# Jumper_Matrix.net
KiCad netlist of a schematic drawn in Altium Designer
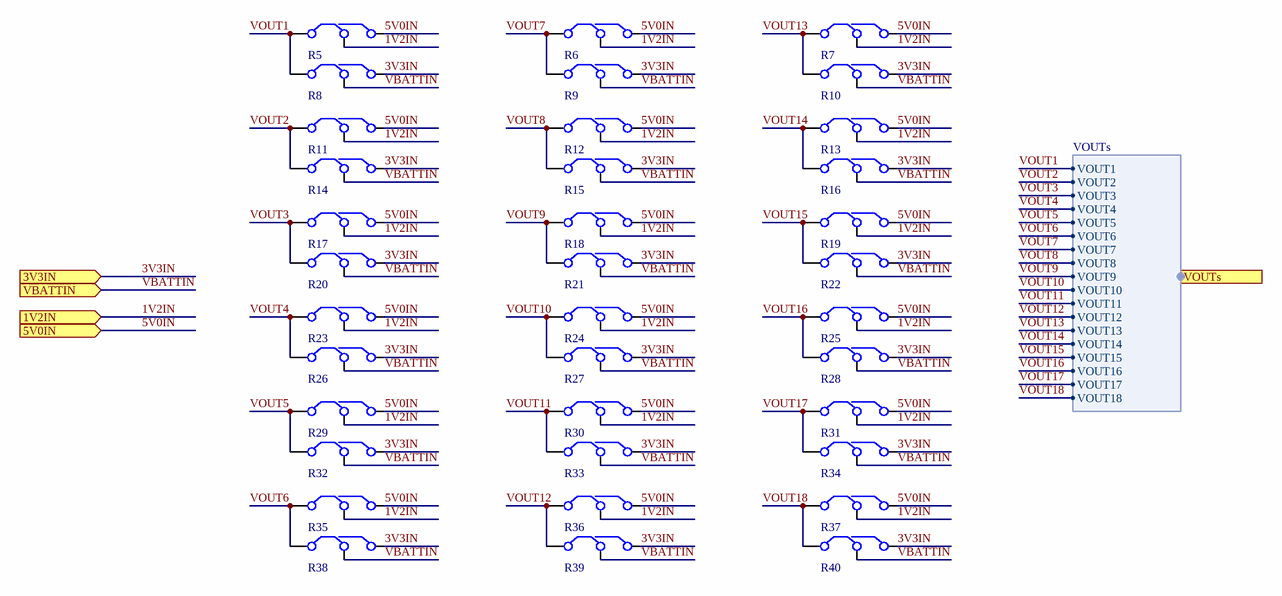
[diagram p0: Jumper Matrix.SchDoc]

(export (version "E")
  (design (tool "Eeschema 10.0.6"))
  (components
    (comp (ref "R5")
      (value "Jumper")
      (footprint "SKP-RMCF1210orRMCF2010")
      (libsource (lib "EPS") (part "PowerRailSelector"))
    )
    (comp (ref "R6")
      (value "Jumper")
      (footprint "SKP-RMCF1210orRMCF2010")
      (libsource (lib "EPS") (part "PowerRailSelector"))
    )
    (comp (ref "R7")
      (value "Jumper")
      (footprint "SKP-RMCF1210orRMCF2010")
      (libsource (lib "EPS") (part "PowerRailSelector"))
    )
    (comp (ref "R8")
      (value "Jumper")
      (footprint "SKP-RMCF1210orRMCF2010")
      (libsource (lib "EPS") (part "PowerRailSelector"))
    )
    (comp (ref "R9")
      (value "Jumper")
      (footprint "SKP-RMCF1210orRMCF2010")
      (libsource (lib "EPS") (part "PowerRailSelector"))
    )
    (comp (ref "R10")
      (value "Jumper")
      (footprint "SKP-RMCF1210orRMCF2010")
      (libsource (lib "EPS") (part "PowerRailSelector"))
    )
    (comp (ref "R11")
      (value "Jumper")
      (footprint "SKP-RMCF1210orRMCF2010")
      (libsource (lib "EPS") (part "PowerRailSelector"))
    )
    (comp (ref "R12")
      (value "Jumper")
      (footprint "SKP-RMCF1210orRMCF2010")
      (libsource (lib "EPS") (part "PowerRailSelector"))
    )
    (comp (ref "R13")
      (value "Jumper")
      (footprint "SKP-RMCF1210orRMCF2010")
      (libsource (lib "EPS") (part "PowerRailSelector"))
    )
    (comp (ref "R14")
      (value "Jumper")
      (footprint "SKP-RMCF1210orRMCF2010")
      (libsource (lib "EPS") (part "PowerRailSelector"))
    )
    (comp (ref "R15")
      (value "Jumper")
      (footprint "SKP-RMCF1210orRMCF2010")
      (libsource (lib "EPS") (part "PowerRailSelector"))
    )
    (comp (ref "R16")
      (value "Jumper")
      (footprint "SKP-RMCF1210orRMCF2010")
      (libsource (lib "EPS") (part "PowerRailSelector"))
    )
    (comp (ref "R17")
      (value "Jumper")
      (footprint "SKP-RMCF1210orRMCF2010")
      (libsource (lib "EPS") (part "PowerRailSelector"))
    )
    (comp (ref "R18")
      (value "Jumper")
      (footprint "SKP-RMCF1210orRMCF2010")
      (libsource (lib "EPS") (part "PowerRailSelector"))
    )
    (comp (ref "R19")
      (value "Jumper")
      (footprint "SKP-RMCF1210orRMCF2010")
      (libsource (lib "EPS") (part "PowerRailSelector"))
    )
    (comp (ref "R20")
      (value "Jumper")
      (footprint "SKP-RMCF1210orRMCF2010")
      (libsource (lib "EPS") (part "PowerRailSelector"))
    )
    (comp (ref "R21")
      (value "Jumper")
      (footprint "SKP-RMCF1210orRMCF2010")
      (libsource (lib "EPS") (part "PowerRailSelector"))
    )
    (comp (ref "R22")
      (value "Jumper")
      (footprint "SKP-RMCF1210orRMCF2010")
      (libsource (lib "EPS") (part "PowerRailSelector"))
    )
    (comp (ref "R23")
      (value "Jumper")
      (footprint "SKP-RMCF1210orRMCF2010")
      (libsource (lib "EPS") (part "PowerRailSelector"))
    )
    (comp (ref "R24")
      (value "Jumper")
      (footprint "SKP-RMCF1210orRMCF2010")
      (libsource (lib "EPS") (part "PowerRailSelector"))
    )
    (comp (ref "R25")
      (value "Jumper")
      (footprint "SKP-RMCF1210orRMCF2010")
      (libsource (lib "EPS") (part "PowerRailSelector"))
    )
    (comp (ref "R26")
      (value "Jumper")
      (footprint "SKP-RMCF1210orRMCF2010")
      (libsource (lib "EPS") (part "PowerRailSelector"))
    )
    (comp (ref "R27")
      (value "Jumper")
      (footprint "SKP-RMCF1210orRMCF2010")
      (libsource (lib "EPS") (part "PowerRailSelector"))
    )
    (comp (ref "R28")
      (value "Jumper")
      (footprint "SKP-RMCF1210orRMCF2010")
      (libsource (lib "EPS") (part "PowerRailSelector"))
    )
    (comp (ref "R29")
      (value "Jumper")
      (footprint "SKP-RMCF1210orRMCF2010")
      (libsource (lib "EPS") (part "PowerRailSelector"))
    )
    (comp (ref "R30")
      (value "Jumper")
      (footprint "SKP-RMCF1210orRMCF2010")
      (libsource (lib "EPS") (part "PowerRailSelector"))
    )
    (comp (ref "R31")
      (value "Jumper")
      (footprint "SKP-RMCF1210orRMCF2010")
      (libsource (lib "EPS") (part "PowerRailSelector"))
    )
    (comp (ref "R32")
      (value "Jumper")
      (footprint "SKP-RMCF1210orRMCF2010")
      (libsource (lib "EPS") (part "PowerRailSelector"))
    )
    (comp (ref "R33")
      (value "Jumper")
      (footprint "SKP-RMCF1210orRMCF2010")
      (libsource (lib "EPS") (part "PowerRailSelector"))
    )
    (comp (ref "R34")
      (value "Jumper")
      (footprint "SKP-RMCF1210orRMCF2010")
      (libsource (lib "EPS") (part "PowerRailSelector"))
    )
    (comp (ref "R35")
      (value "Jumper")
      (footprint "SKP-RMCF1210orRMCF2010")
      (libsource (lib "EPS") (part "PowerRailSelector"))
    )
    (comp (ref "R36")
      (value "Jumper")
      (footprint "SKP-RMCF1210orRMCF2010")
      (libsource (lib "EPS") (part "PowerRailSelector"))
    )
    (comp (ref "R37")
      (value "Jumper")
      (footprint "SKP-RMCF1210orRMCF2010")
      (libsource (lib "EPS") (part "PowerRailSelector"))
    )
    (comp (ref "R38")
      (value "Jumper")
      (footprint "SKP-RMCF1210orRMCF2010")
      (libsource (lib "EPS") (part "PowerRailSelector"))
    )
    (comp (ref "R39")
      (value "Jumper")
      (footprint "SKP-RMCF1210orRMCF2010")
      (libsource (lib "EPS") (part "PowerRailSelector"))
    )
    (comp (ref "R40")
      (value "Jumper")
      (footprint "SKP-RMCF1210orRMCF2010")
      (libsource (lib "EPS") (part "PowerRailSelector"))
    )
  )
  (nets
    (net (code "2") (name "/1V2IN") (class "Default")
      (node (ref "R11") (pin "2") (pintype "passive"))
      (node (ref "R12") (pin "2") (pintype "passive"))
      (node (ref "R13") (pin "2") (pintype "passive"))
      (node (ref "R17") (pin "2") (pintype "passive"))
      (node (ref "R18") (pin "2") (pintype "passive"))
      (node (ref "R19") (pin "2") (pintype "passive"))
      (node (ref "R23") (pin "2") (pintype "passive"))
      (node (ref "R24") (pin "2") (pintype "passive"))
      (node (ref "R25") (pin "2") (pintype "passive"))
      (node (ref "R29") (pin "2") (pintype "passive"))
      (node (ref "R30") (pin "2") (pintype "passive"))
      (node (ref "R31") (pin "2") (pintype "passive"))
      (node (ref "R35") (pin "2") (pintype "passive"))
      (node (ref "R36") (pin "2") (pintype "passive"))
      (node (ref "R37") (pin "2") (pintype "passive"))
      (node (ref "R5") (pin "2") (pintype "passive"))
      (node (ref "R6") (pin "2") (pintype "passive"))
      (node (ref "R7") (pin "2") (pintype "passive"))
    )
    (net (code "3") (name "/3V3IN") (class "Default")
      (node (ref "R10") (pin "3") (pintype "passive"))
      (node (ref "R14") (pin "3") (pintype "passive"))
      (node (ref "R15") (pin "3") (pintype "passive"))
      (node (ref "R16") (pin "3") (pintype "passive"))
      (node (ref "R20") (pin "3") (pintype "passive"))
      (node (ref "R21") (pin "3") (pintype "passive"))
      (node (ref "R22") (pin "3") (pintype "passive"))
      (node (ref "R26") (pin "3") (pintype "passive"))
      (node (ref "R27") (pin "3") (pintype "passive"))
      (node (ref "R28") (pin "3") (pintype "passive"))
      (node (ref "R32") (pin "3") (pintype "passive"))
      (node (ref "R33") (pin "3") (pintype "passive"))
      (node (ref "R34") (pin "3") (pintype "passive"))
      (node (ref "R38") (pin "3") (pintype "passive"))
      (node (ref "R39") (pin "3") (pintype "passive"))
      (node (ref "R40") (pin "3") (pintype "passive"))
      (node (ref "R8") (pin "3") (pintype "passive"))
      (node (ref "R9") (pin "3") (pintype "passive"))
    )
    (net (code "4") (name "/5V0IN") (class "Default")
      (node (ref "R11") (pin "3") (pintype "passive"))
      (node (ref "R12") (pin "3") (pintype "passive"))
      (node (ref "R13") (pin "3") (pintype "passive"))
      (node (ref "R17") (pin "3") (pintype "passive"))
      (node (ref "R18") (pin "3") (pintype "passive"))
      (node (ref "R19") (pin "3") (pintype "passive"))
      (node (ref "R23") (pin "3") (pintype "passive"))
      (node (ref "R24") (pin "3") (pintype "passive"))
      (node (ref "R25") (pin "3") (pintype "passive"))
      (node (ref "R29") (pin "3") (pintype "passive"))
      (node (ref "R30") (pin "3") (pintype "passive"))
      (node (ref "R31") (pin "3") (pintype "passive"))
      (node (ref "R35") (pin "3") (pintype "passive"))
      (node (ref "R36") (pin "3") (pintype "passive"))
      (node (ref "R37") (pin "3") (pintype "passive"))
      (node (ref "R5") (pin "3") (pintype "passive"))
      (node (ref "R6") (pin "3") (pintype "passive"))
      (node (ref "R7") (pin "3") (pintype "passive"))
    )
    (net (code "5") (name "/VBATTIN") (class "Default")
      (node (ref "R10") (pin "2") (pintype "passive"))
      (node (ref "R14") (pin "2") (pintype "passive"))
      (node (ref "R15") (pin "2") (pintype "passive"))
      (node (ref "R16") (pin "2") (pintype "passive"))
      (node (ref "R20") (pin "2") (pintype "passive"))
      (node (ref "R21") (pin "2") (pintype "passive"))
      (node (ref "R22") (pin "2") (pintype "passive"))
      (node (ref "R26") (pin "2") (pintype "passive"))
      (node (ref "R27") (pin "2") (pintype "passive"))
      (node (ref "R28") (pin "2") (pintype "passive"))
      (node (ref "R32") (pin "2") (pintype "passive"))
      (node (ref "R33") (pin "2") (pintype "passive"))
      (node (ref "R34") (pin "2") (pintype "passive"))
      (node (ref "R38") (pin "2") (pintype "passive"))
      (node (ref "R39") (pin "2") (pintype "passive"))
      (node (ref "R40") (pin "2") (pintype "passive"))
      (node (ref "R8") (pin "2") (pintype "passive"))
      (node (ref "R9") (pin "2") (pintype "passive"))
    )
    (net (code "6") (name "/VOUT1") (class "Default")
      (node (ref "R5") (pin "1") (pintype "passive"))
      (node (ref "R8") (pin "1") (pintype "passive"))
    )
    (net (code "7") (name "/VOUT2") (class "Default")
      (node (ref "R11") (pin "1") (pintype "passive"))
      (node (ref "R14") (pin "1") (pintype "passive"))
    )
    (net (code "8") (name "/VOUT3") (class "Default")
      (node (ref "R17") (pin "1") (pintype "passive"))
      (node (ref "R20") (pin "1") (pintype "passive"))
    )
    (net (code "9") (name "/VOUT4") (class "Default")
      (node (ref "R23") (pin "1") (pintype "passive"))
      (node (ref "R26") (pin "1") (pintype "passive"))
    )
    (net (code "10") (name "/VOUT5") (class "Default")
      (node (ref "R29") (pin "1") (pintype "passive"))
      (node (ref "R32") (pin "1") (pintype "passive"))
    )
    (net (code "11") (name "/VOUT6") (class "Default")
      (node (ref "R35") (pin "1") (pintype "passive"))
      (node (ref "R38") (pin "1") (pintype "passive"))
    )
    (net (code "12") (name "/VOUT7") (class "Default")
      (node (ref "R6") (pin "1") (pintype "passive"))
      (node (ref "R9") (pin "1") (pintype "passive"))
    )
    (net (code "13") (name "/VOUT8") (class "Default")
      (node (ref "R12") (pin "1") (pintype "passive"))
      (node (ref "R15") (pin "1") (pintype "passive"))
    )
    (net (code "14") (name "/VOUT9") (class "Default")
      (node (ref "R18") (pin "1") (pintype "passive"))
      (node (ref "R21") (pin "1") (pintype "passive"))
    )
    (net (code "15") (name "/VOUT10") (class "Default")
      (node (ref "R24") (pin "1") (pintype "passive"))
      (node (ref "R27") (pin "1") (pintype "passive"))
    )
    (net (code "16") (name "/VOUT11") (class "Default")
      (node (ref "R30") (pin "1") (pintype "passive"))
      (node (ref "R33") (pin "1") (pintype "passive"))
    )
    (net (code "17") (name "/VOUT12") (class "Default")
      (node (ref "R36") (pin "1") (pintype "passive"))
      (node (ref "R39") (pin "1") (pintype "passive"))
    )
    (net (code "18") (name "/VOUT13") (class "Default")
      (node (ref "R10") (pin "1") (pintype "passive"))
      (node (ref "R7") (pin "1") (pintype "passive"))
    )
    (net (code "19") (name "/VOUT14") (class "Default")
      (node (ref "R13") (pin "1") (pintype "passive"))
      (node (ref "R16") (pin "1") (pintype "passive"))
    )
    (net (code "20") (name "/VOUT15") (class "Default")
      (node (ref "R19") (pin "1") (pintype "passive"))
      (node (ref "R22") (pin "1") (pintype "passive"))
    )
    (net (code "21") (name "/VOUT16") (class "Default")
      (node (ref "R25") (pin "1") (pintype "passive"))
      (node (ref "R28") (pin "1") (pintype "passive"))
    )
    (net (code "22") (name "/VOUT17") (class "Default")
      (node (ref "R31") (pin "1") (pintype "passive"))
      (node (ref "R34") (pin "1") (pintype "passive"))
    )
    (net (code "23") (name "/VOUT18") (class "Default")
      (node (ref "R37") (pin "1") (pintype "passive"))
      (node (ref "R40") (pin "1") (pintype "passive"))
    )
  )
)
